# Scriptable_Guitar_Pedal.net
KiCad netlist of a schematic drawn in EAGLE
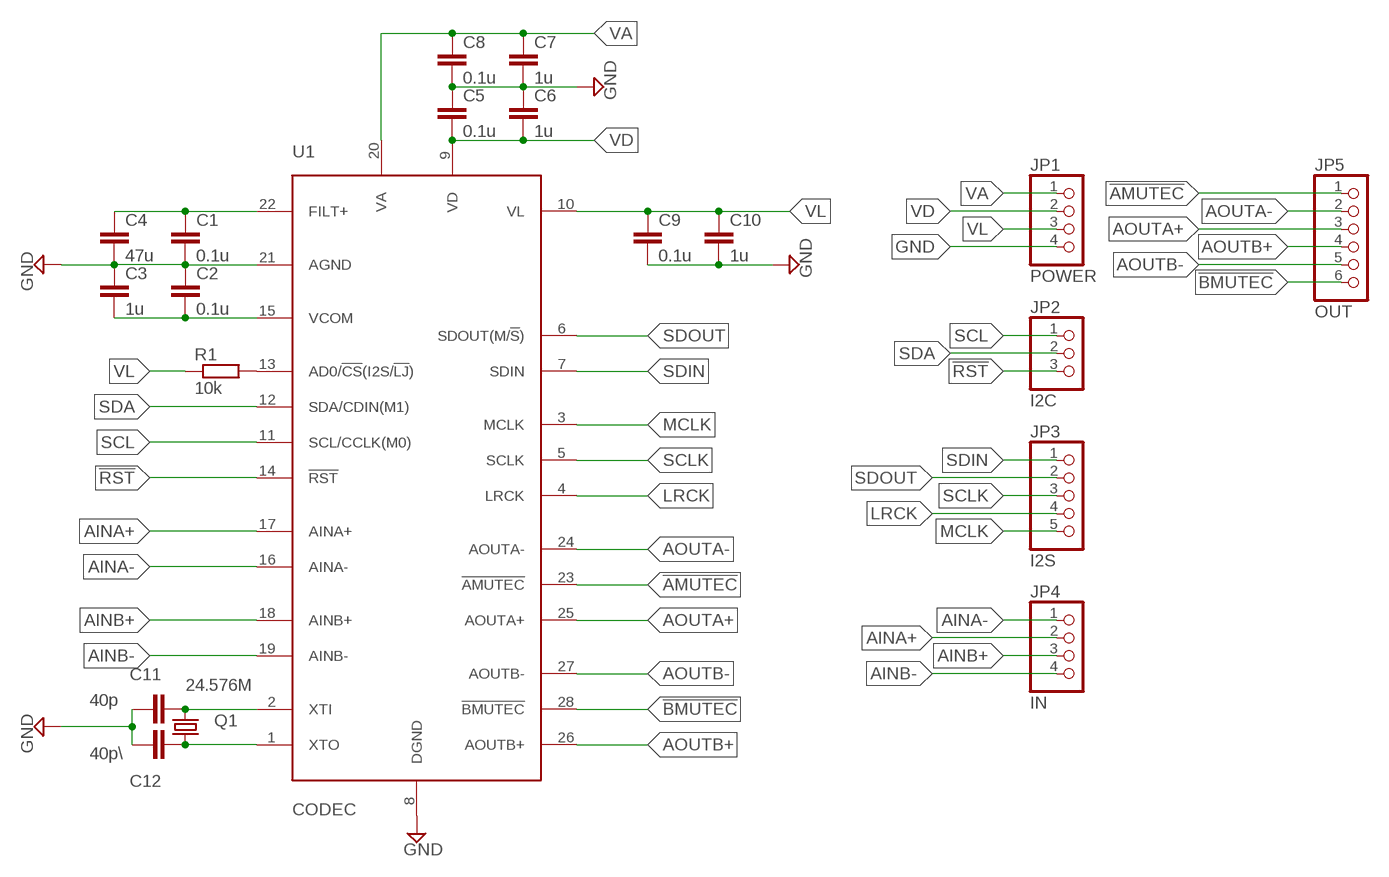
[diagram p0: schematic, sheet 1]

(export (version "E")
  (design (tool "Eeschema 10.0.6"))
  (components
    (comp (ref "C1")
      (value "0.1u")
      (footprint "eagle-import:C0603")
      (libsource (lib "eagle-import") (part "C-EUC0603"))
    )
    (comp (ref "C2")
      (value "0.1u")
      (footprint "eagle-import:C0603")
      (libsource (lib "eagle-import") (part "C-EUC0603"))
    )
    (comp (ref "C3")
      (value "1u")
      (footprint "eagle-import:C0603")
      (libsource (lib "eagle-import") (part "C-EUC0603"))
    )
    (comp (ref "C4")
      (value "47u")
      (footprint "eagle-import:C0603")
      (libsource (lib "eagle-import") (part "C-EUC0603"))
    )
    (comp (ref "C5")
      (value "0.1u")
      (footprint "eagle-import:C0603")
      (libsource (lib "eagle-import") (part "C-EUC0603"))
    )
    (comp (ref "C6")
      (value "1u")
      (footprint "eagle-import:C0603")
      (libsource (lib "eagle-import") (part "C-EUC0603"))
    )
    (comp (ref "C7")
      (value "1u")
      (footprint "eagle-import:C0603")
      (libsource (lib "eagle-import") (part "C-EUC0603"))
    )
    (comp (ref "C8")
      (value "0.1u")
      (footprint "eagle-import:C0603")
      (libsource (lib "eagle-import") (part "C-EUC0603"))
    )
    (comp (ref "C9")
      (value "0.1u")
      (footprint "eagle-import:C0603")
      (libsource (lib "eagle-import") (part "C-EUC0603"))
    )
    (comp (ref "C10")
      (value "1u")
      (footprint "eagle-import:C0603")
      (libsource (lib "eagle-import") (part "C-EUC0603"))
    )
    (comp (ref "C11")
      (value "40p")
      (footprint "eagle-import:C0603")
      (libsource (lib "eagle-import") (part "C-EUC0603"))
    )
    (comp (ref "C12")
      (value "40p\\")
      (footprint "eagle-import:C0603")
      (libsource (lib "eagle-import") (part "C-EUC0603"))
    )
    (comp (ref "JP1")
      (value "POWER")
      (footprint "eagle-import:1X04")
      (libsource (lib "eagle-import") (part "PINHD-1X4"))
    )
    (comp (ref "JP2")
      (value "I2C")
      (footprint "eagle-import:1X03")
      (libsource (lib "eagle-import") (part "PINHD-1X3"))
    )
    (comp (ref "JP3")
      (value "I2S")
      (footprint "eagle-import:1X05")
      (libsource (lib "eagle-import") (part "PINHD-1X5"))
    )
    (comp (ref "JP4")
      (value "IN")
      (footprint "eagle-import:1X04")
      (libsource (lib "eagle-import") (part "PINHD-1X4"))
    )
    (comp (ref "JP5")
      (value "OUT")
      (footprint "eagle-import:1X06")
      (libsource (lib "eagle-import") (part "PINHD-1X6"))
    )
    (comp (ref "Q1")
      (value "24.576M")
      (footprint "eagle-import:HC49U-V")
      (libsource (lib "eagle-import") (part "CRYSTALHC49U-V"))
    )
    (comp (ref "R1")
      (value "10k")
      (footprint "eagle-import:R0603")
      (libsource (lib "eagle-import") (part "R-EU_R0603"))
    )
    (comp (ref "U1")
      (value "CODEC")
      (footprint "eagle-import:TSSOP-28")
      (libsource (lib "eagle-import") (part "CS4272"))
    )
  )
  (nets
    (net (code "1") (name "/~{AMUTEC}") (class "Default")
      (node (ref "JP5") (pin "1") (pinfunction "1_1") (pintype "passive"))
      (node (ref "U1") (pin "23") (pinfunction "~{AMUTEC}_23") (pintype "output"))
    )
    (net (code "2") (name "/~{BMUTEC}") (class "Default")
      (node (ref "JP5") (pin "6") (pinfunction "6_6") (pintype "passive"))
      (node (ref "U1") (pin "28") (pinfunction "~{BMUTEC}_28") (pintype "output"))
    )
    (net (code "3") (name "/~{RST}") (class "Default")
      (node (ref "JP2") (pin "3") (pinfunction "3_3") (pintype "passive"))
      (node (ref "U1") (pin "14") (pinfunction "~{RST}_14") (pintype "input"))
    )
    (net (code "4") (name "AINA+") (class "Default")
      (node (ref "JP4") (pin "2") (pinfunction "2_2") (pintype "passive"))
      (node (ref "U1") (pin "17") (pinfunction "AINA+_17") (pintype "input"))
    )
    (net (code "5") (name "AINA-") (class "Default")
      (node (ref "JP4") (pin "1") (pinfunction "1_1") (pintype "passive"))
      (node (ref "U1") (pin "16") (pinfunction "AINA-_16") (pintype "input"))
    )
    (net (code "6") (name "AINB+") (class "Default")
      (node (ref "JP4") (pin "3") (pinfunction "3_3") (pintype "passive"))
      (node (ref "U1") (pin "18") (pinfunction "AINB+_18") (pintype "input"))
    )
    (net (code "7") (name "AINB-") (class "Default")
      (node (ref "JP4") (pin "4") (pinfunction "4_4") (pintype "passive"))
      (node (ref "U1") (pin "19") (pinfunction "AINB-_19") (pintype "input"))
    )
    (net (code "8") (name "AOUTA+") (class "Default")
      (node (ref "JP5") (pin "3") (pinfunction "3_3") (pintype "passive"))
      (node (ref "U1") (pin "25") (pinfunction "AOUTA+_25") (pintype "output"))
    )
    (net (code "9") (name "AOUTA-") (class "Default")
      (node (ref "JP5") (pin "2") (pinfunction "2_2") (pintype "passive"))
      (node (ref "U1") (pin "24") (pinfunction "AOUTA-_24") (pintype "output"))
    )
    (net (code "10") (name "AOUTB+") (class "Default")
      (node (ref "JP5") (pin "4") (pinfunction "4_4") (pintype "passive"))
      (node (ref "U1") (pin "26") (pinfunction "AOUTB+_26") (pintype "output"))
    )
    (net (code "11") (name "AOUTB-") (class "Default")
      (node (ref "JP5") (pin "5") (pinfunction "5_5") (pintype "passive"))
      (node (ref "U1") (pin "27") (pinfunction "AOUTB-_27") (pintype "output"))
    )
    (net (code "12") (name "GND") (class "Default")
      (node (ref "C1") (pin "2") (pinfunction "2_2") (pintype "passive"))
      (node (ref "C10") (pin "2") (pinfunction "2_2") (pintype "passive"))
      (node (ref "C11") (pin "1") (pinfunction "1_1") (pintype "passive"))
      (node (ref "C12") (pin "1") (pinfunction "1_1") (pintype "passive"))
      (node (ref "C2") (pin "1") (pinfunction "1_1") (pintype "passive"))
      (node (ref "C3") (pin "1") (pinfunction "1_1") (pintype "passive"))
      (node (ref "C4") (pin "2") (pinfunction "2_2") (pintype "passive"))
      (node (ref "C5") (pin "1") (pinfunction "1_1") (pintype "passive"))
      (node (ref "C6") (pin "1") (pinfunction "1_1") (pintype "passive"))
      (node (ref "C7") (pin "2") (pinfunction "2_2") (pintype "passive"))
      (node (ref "C8") (pin "2") (pinfunction "2_2") (pintype "passive"))
      (node (ref "C9") (pin "2") (pinfunction "2_2") (pintype "passive"))
      (node (ref "JP1") (pin "4") (pinfunction "4_4") (pintype "passive"))
      (node (ref "U1") (pin "21") (pinfunction "AGND_21") (pintype "bidirectional"))
      (node (ref "U1") (pin "8") (pinfunction "DGND_8") (pintype "input"))
    )
    (net (code "13") (name "LRCK") (class "Default")
      (node (ref "JP3") (pin "4") (pinfunction "4_4") (pintype "passive"))
      (node (ref "U1") (pin "4") (pinfunction "LRCK_4") (pintype "bidirectional"))
    )
    (net (code "14") (name "MCLK") (class "Default")
      (node (ref "JP3") (pin "5") (pinfunction "5_5") (pintype "passive"))
      (node (ref "U1") (pin "3") (pinfunction "MCLK_3") (pintype "bidirectional"))
    )
    (net (code "15") (name "Net-(U1-AD0{slash}~{CS}(I2S{slash}~{LJ}))") (class "Default")
      (node (ref "R1") (pin "2") (pinfunction "2_2") (pintype "passive"))
      (node (ref "U1") (pin "13") (pinfunction "AD0/~{CS}(I2S/~{LJ})_13") (pintype "input"))
    )
    (net (code "16") (name "Net-(U1-FILT+)") (class "Default")
      (node (ref "C1") (pin "1") (pinfunction "1_1") (pintype "passive"))
      (node (ref "C4") (pin "1") (pinfunction "1_1") (pintype "passive"))
      (node (ref "U1") (pin "22") (pinfunction "FILT+_22") (pintype "output"))
    )
    (net (code "17") (name "Net-(U1-VCOM)") (class "Default")
      (node (ref "C2") (pin "2") (pinfunction "2_2") (pintype "passive"))
      (node (ref "C3") (pin "2") (pinfunction "2_2") (pintype "passive"))
      (node (ref "U1") (pin "15") (pinfunction "VCOM_15") (pintype "output"))
    )
    (net (code "18") (name "Net-(U1-XTI)") (class "Default")
      (node (ref "C11") (pin "2") (pinfunction "2_2") (pintype "passive"))
      (node (ref "Q1") (pin "2") (pinfunction "2_2") (pintype "passive"))
      (node (ref "U1") (pin "2") (pinfunction "XTI_2") (pintype "bidirectional"))
    )
    (net (code "19") (name "Net-(U1-XTO)") (class "Default")
      (node (ref "C12") (pin "2") (pinfunction "2_2") (pintype "passive"))
      (node (ref "Q1") (pin "1") (pinfunction "1_1") (pintype "passive"))
      (node (ref "U1") (pin "1") (pinfunction "XTO_1") (pintype "bidirectional"))
    )
    (net (code "20") (name "SCL") (class "Default")
      (node (ref "JP2") (pin "1") (pinfunction "1_1") (pintype "passive"))
      (node (ref "U1") (pin "11") (pinfunction "SCL/CCLK(M0)_11") (pintype "input"))
    )
    (net (code "21") (name "SCLK") (class "Default")
      (node (ref "JP3") (pin "3") (pinfunction "3_3") (pintype "passive"))
      (node (ref "U1") (pin "5") (pinfunction "SCLK_5") (pintype "bidirectional"))
    )
    (net (code "22") (name "SDA") (class "Default")
      (node (ref "JP2") (pin "2") (pinfunction "2_2") (pintype "passive"))
      (node (ref "U1") (pin "12") (pinfunction "SDA/CDIN(M1)_12") (pintype "bidirectional"))
    )
    (net (code "23") (name "SDIN") (class "Default")
      (node (ref "JP3") (pin "1") (pinfunction "1_1") (pintype "passive"))
      (node (ref "U1") (pin "7") (pinfunction "SDIN_7") (pintype "input"))
    )
    (net (code "24") (name "SDOUT") (class "Default")
      (node (ref "JP3") (pin "2") (pinfunction "2_2") (pintype "passive"))
      (node (ref "U1") (pin "6") (pinfunction "SDOUT(M/~{S})_6") (pintype "output"))
    )
    (net (code "25") (name "VA") (class "Default")
      (node (ref "C7") (pin "1") (pinfunction "1_1") (pintype "passive"))
      (node (ref "C8") (pin "1") (pinfunction "1_1") (pintype "passive"))
      (node (ref "JP1") (pin "1") (pinfunction "1_1") (pintype "passive"))
      (node (ref "U1") (pin "20") (pinfunction "VA_20") (pintype "input"))
    )
    (net (code "26") (name "VD") (class "Default")
      (node (ref "C5") (pin "2") (pinfunction "2_2") (pintype "passive"))
      (node (ref "C6") (pin "2") (pinfunction "2_2") (pintype "passive"))
      (node (ref "JP1") (pin "2") (pinfunction "2_2") (pintype "passive"))
      (node (ref "U1") (pin "9") (pinfunction "VD_9") (pintype "input"))
    )
    (net (code "27") (name "VL") (class "Default")
      (node (ref "C10") (pin "1") (pinfunction "1_1") (pintype "passive"))
      (node (ref "C9") (pin "1") (pinfunction "1_1") (pintype "passive"))
      (node (ref "JP1") (pin "3") (pinfunction "3_3") (pintype "passive"))
      (node (ref "R1") (pin "1") (pinfunction "1_1") (pintype "passive"))
      (node (ref "U1") (pin "10") (pinfunction "VL_10") (pintype "input"))
    )
  )
)
